# Pack_switch.net
KiCad netlist of a schematic drawn in Altium Designer
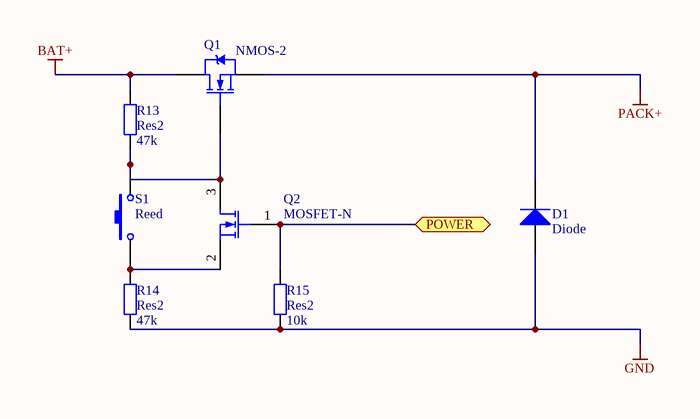
[diagram p0: Pack switch.SchDoc]

(export (version "E")
  (design (tool "Eeschema 10.0.6"))
  (components
    (comp (ref "D1")
      (value "Diode")
      (footprint "SMC")
      (description "Default Diode")
      (fields (field (name "PART") "multicomp s3k"))
      (libsource (lib "Miscellaneous Devices") (part "Diode"))
    )
    (comp (ref "Q1")
      (value "NMOS-2")
      (footprint "TO_263")
      (description "N-Channel Power MOSFET")
      (fields (field (name "PART") "sum110p04-05-e3"))
      (libsource (lib "Miscellaneous Devices") (part "NMOS-2"))
    )
    (comp (ref "Q2")
      (value "MOSFET-N")
      (footprint "2N7002")
      (description "NXP - 2N7002 - MOSFET,N CH, 60V,0.3A,SOT23")
      (libsource (lib "2N7002") (part "2N7002"))
    )
    (comp (ref "R13")
      (value "Res2")
      (footprint "0603")
      (description "Resistor")
      (fields (field (name "ALTIUM_VALUE") "47k") (field (name "PUBLISHER") "Altium Limited"))
      (libsource (lib "Miscellaneous Devices") (part "Res2"))
    )
    (comp (ref "R14")
      (value "Res2")
      (footprint "0603")
      (description "Resistor")
      (fields (field (name "ALTIUM_VALUE") "47k") (field (name "PUBLISHER") "Altium Limited"))
      (libsource (lib "Miscellaneous Devices") (part "Res2"))
    )
    (comp (ref "R15")
      (value "Res2")
      (footprint "0603")
      (description "Resistor")
      (fields (field (name "ALTIUM_VALUE") "10k") (field (name "PUBLISHER") "Altium Limited"))
      (libsource (lib "Miscellaneous Devices") (part "Res2"))
    )
    (comp (ref "S1")
      (value "Reed")
      (footprint "SPST-2")
      (description "Switch")
      (fields (field (name "PART") "hamlim 59025-4-s-02-a"))
      (libsource (lib "Miscellaneous Devices") (part "SW-PB"))
    )
  )
  (nets
    (net (code "1") (name "/POWER") (class "Default")
      (node (ref "Q2") (pin "1") (pinfunction "G_1") (pintype "passive"))
      (node (ref "R15") (pin "2") (pinfunction "2_2") (pintype "passive"))
    )
    (net (code "2") (name "BAT+") (class "Default")
      (node (ref "Q1") (pin "2") (pinfunction "D_2") (pintype "passive"))
      (node (ref "R13") (pin "2") (pinfunction "2_2") (pintype "passive"))
    )
    (net (code "3") (name "GND") (class "Default")
      (node (ref "D1") (pin "1") (pinfunction "A_1") (pintype "passive"))
      (node (ref "R14") (pin "1") (pinfunction "1_1") (pintype "passive"))
      (node (ref "R15") (pin "1") (pinfunction "1_1") (pintype "passive"))
    )
    (net (code "4") (name "Net-(Q1-G)") (class "Default")
      (node (ref "Q1") (pin "1") (pinfunction "G_1") (pintype "passive"))
      (node (ref "Q2") (pin "3") (pinfunction "D_3") (pintype "passive"))
      (node (ref "R13") (pin "1") (pinfunction "1_1") (pintype "passive"))
      (node (ref "S1") (pin "2") (pinfunction "2_2") (pintype "passive"))
    )
    (net (code "5") (name "Net-(Q2-S)") (class "Default")
      (node (ref "Q2") (pin "2") (pinfunction "S_2") (pintype "passive"))
      (node (ref "R14") (pin "2") (pinfunction "2_2") (pintype "passive"))
      (node (ref "S1") (pin "1") (pinfunction "1_1") (pintype "passive"))
    )
    (net (code "6") (name "PACK+") (class "Default")
      (node (ref "D1") (pin "2") (pinfunction "K_2") (pintype "passive"))
      (node (ref "Q1") (pin "3") (pinfunction "S_3") (pintype "passive"))
    )
  )
)
